# Analog_Switch_Arrays.net
KiCad netlist of a schematic drawn in Altium Designer
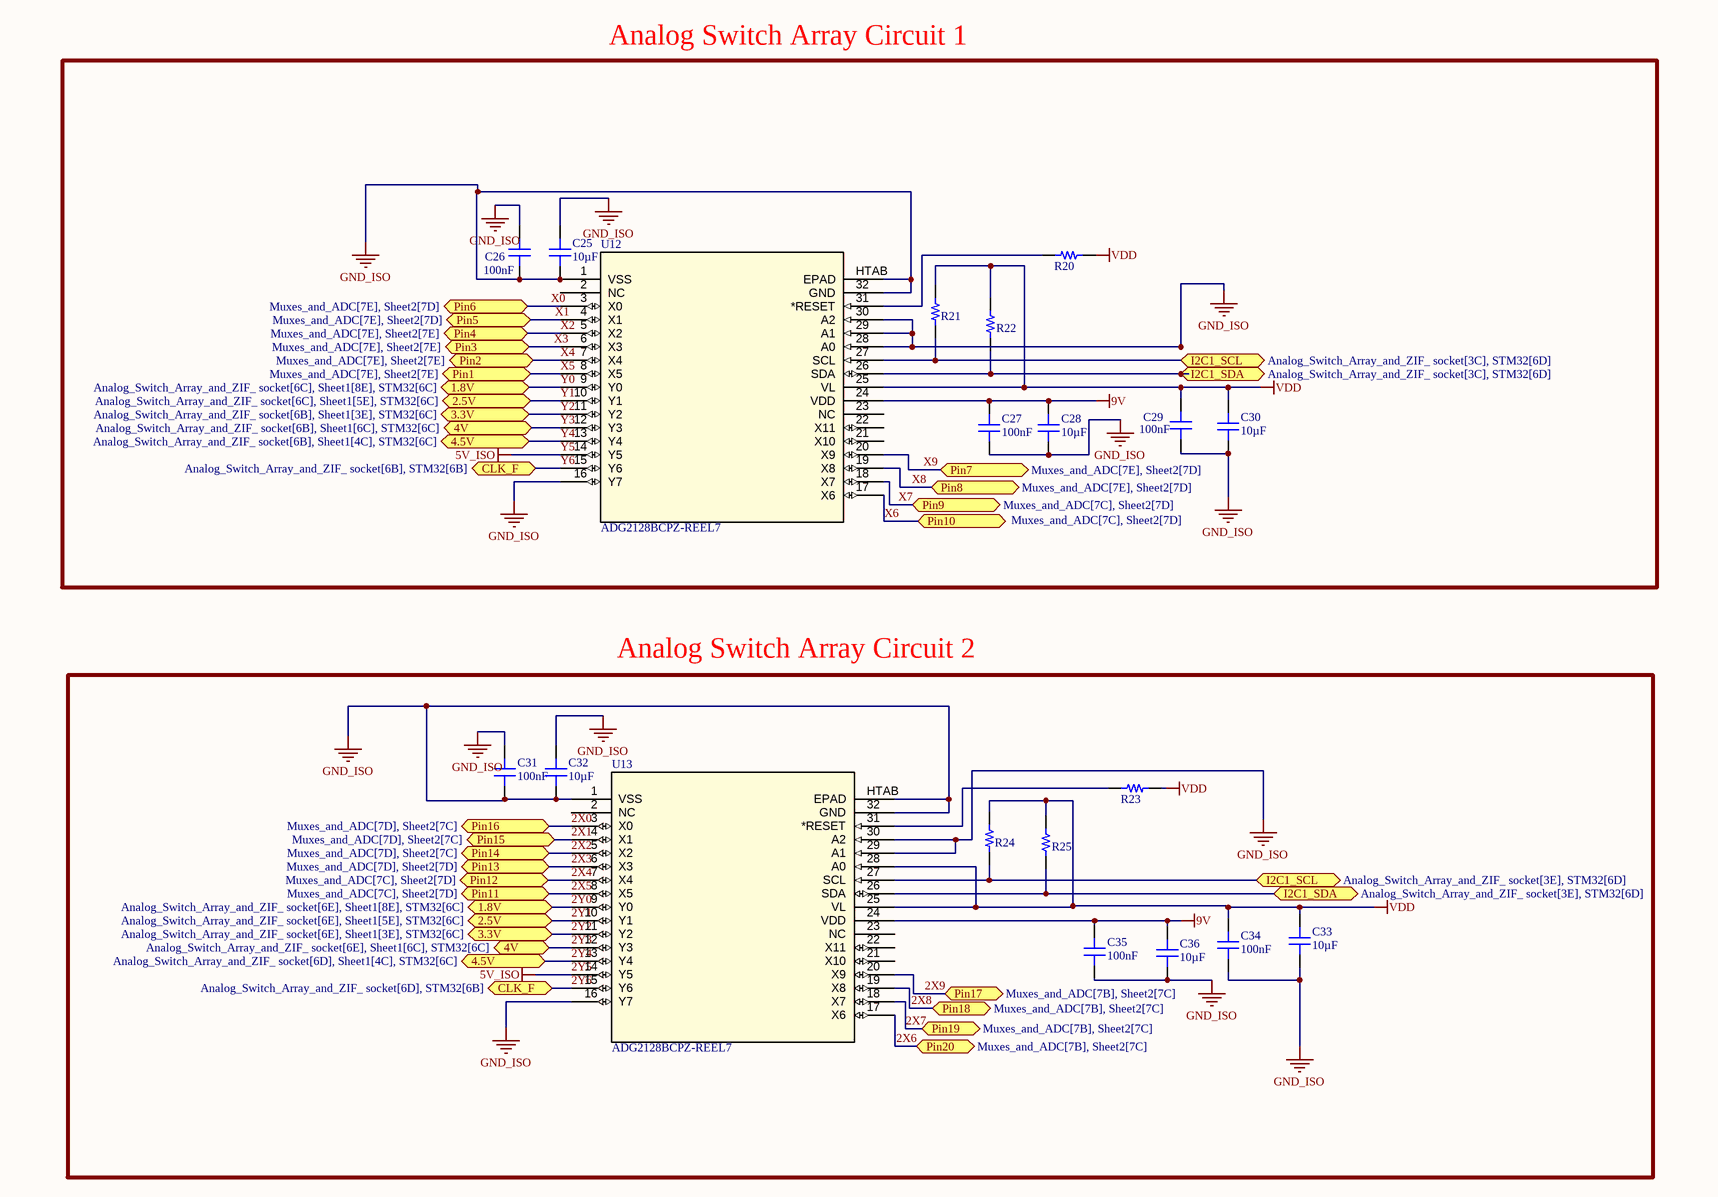
[diagram p0: Analog_Switch_Arrays.SchDoc]

(export (version "E")
  (design (tool "Eeschema 10.0.6"))
  (components
    (comp (ref "C25")
      (value "10µF")
      (footprint "MURATA CAP GCM31M 1206_3216")
      (description "CAP CER 10UF 35V X8M 1206")
      (fields (field (name "PART NUMBER") "GCM31CM8EG106KE08L"))
      (libsource (lib "University of Massachusetts Lowell") (part "CAPACITOR"))
    )
    (comp (ref "C26")
      (value "100nF")
      (footprint "CAP 1206_3216 - 0.8MM")
      (description "CAP CER 1206 0.1F 16V ULTRA STAB")
      (fields (field (name "PART NUMBER") "C1206X104G4HAC7800"))
      (libsource (lib "University of Massachusetts Lowell") (part "CAPACITOR"))
    )
    (comp (ref "C27")
      (value "100nF")
      (footprint "CAP 1206_3216 - 0.8MM")
      (description "CAP CER 1206 0.1F 16V ULTRA STAB")
      (fields (field (name "PART NUMBER") "C1206X104G4HAC7800"))
      (libsource (lib "University of Massachusetts Lowell") (part "CAPACITOR"))
    )
    (comp (ref "C28")
      (value "10µF")
      (footprint "MURATA CAP GCM31M 1206_3216")
      (description "CAP CER 10UF 35V X8M 1206")
      (fields (field (name "PART NUMBER") "GCM31CM8EG106KE08L"))
      (libsource (lib "University of Massachusetts Lowell") (part "CAPACITOR"))
    )
    (comp (ref "C29")
      (value "100nF")
      (footprint "CAP 1206_3216 - 0.8MM")
      (description "CAP CER 1206 0.1F 16V ULTRA STAB")
      (fields (field (name "PART NUMBER") "C1206X104G4HAC7800"))
      (libsource (lib "University of Massachusetts Lowell") (part "CAPACITOR"))
    )
    (comp (ref "C30")
      (value "10µF")
      (footprint "MURATA CAP GCM31M 1206_3216")
      (description "CAP CER 10UF 35V X8M 1206")
      (fields (field (name "PART NUMBER") "GCM31CM8EG106KE08L"))
      (libsource (lib "University of Massachusetts Lowell") (part "CAPACITOR"))
    )
    (comp (ref "C31")
      (value "100nF")
      (footprint "CAP 1206_3216 - 0.8MM")
      (description "CAP CER 1206 0.1F 16V ULTRA STAB")
      (fields (field (name "PART NUMBER") "C1206X104G4HAC7800"))
      (libsource (lib "University of Massachusetts Lowell") (part "CAPACITOR"))
    )
    (comp (ref "C32")
      (value "10µF")
      (footprint "MURATA CAP GCM31M 1206_3216")
      (description "CAP CER 10UF 35V X8M 1206")
      (fields (field (name "PART NUMBER") "GCM31CM8EG106KE08L"))
      (libsource (lib "University of Massachusetts Lowell") (part "CAPACITOR"))
    )
    (comp (ref "C33")
      (value "10µF")
      (footprint "MURATA CAP GCM31M 1206_3216")
      (description "CAP CER 10UF 35V X8M 1206")
      (fields (field (name "PART NUMBER") "GCM31CM8EG106KE08L"))
      (libsource (lib "University of Massachusetts Lowell") (part "CAPACITOR"))
    )
    (comp (ref "C34")
      (value "100nF")
      (footprint "CAP 1206_3216 - 0.8MM")
      (description "CAP CER 1206 0.1F 16V ULTRA STAB")
      (fields (field (name "PART NUMBER") "C1206X104G4HAC7800"))
      (libsource (lib "University of Massachusetts Lowell") (part "CAPACITOR"))
    )
    (comp (ref "C35")
      (value "100nF")
      (footprint "CAP 1206_3216 - 0.8MM")
      (description "CAP CER 1206 0.1F 16V ULTRA STAB")
      (fields (field (name "PART NUMBER") "C1206X104G4HAC7800"))
      (libsource (lib "University of Massachusetts Lowell") (part "CAPACITOR"))
    )
    (comp (ref "C36")
      (value "10µF")
      (footprint "MURATA CAP GCM31M 1206_3216")
      (description "CAP CER 10UF 35V X8M 1206")
      (fields (field (name "PART NUMBER") "GCM31CM8EG106KE08L"))
      (libsource (lib "University of Massachusetts Lowell") (part "CAPACITOR"))
    )
    (comp (ref "R20")
      (value "RP1206BRD0710KL")
      (footprint "YAGEO RES 1206_3216")
      (description "RES 10K OHM 0.1% 1/4W 1206")
      (libsource (lib "University of Massachusetts Lowell") (part "RESISTOR"))
    )
    (comp (ref "R21")
      (value "SG732ETTD222K")
      (footprint "RES 1210_3225")
      (description "RES 2.2K OHM 10% 1/2W 1210")
      (libsource (lib "University of Massachusetts Lowell") (part "RESISTOR"))
    )
    (comp (ref "R22")
      (value "SG732ETTD222K")
      (footprint "RES 1210_3225")
      (description "RES 2.2K OHM 10% 1/2W 1210")
      (libsource (lib "University of Massachusetts Lowell") (part "RESISTOR"))
    )
    (comp (ref "R23")
      (value "RP1206BRD0710KL")
      (footprint "YAGEO RES 1206_3216")
      (description "RES 10K OHM 0.1% 1/4W 1206")
      (libsource (lib "University of Massachusetts Lowell") (part "RESISTOR"))
    )
    (comp (ref "R24")
      (value "SG732ETTD222K")
      (footprint "RES 1210_3225")
      (description "RES 2.2K OHM 10% 1/2W 1210")
      (libsource (lib "University of Massachusetts Lowell") (part "RESISTOR"))
    )
    (comp (ref "R25")
      (value "SG732ETTD222K")
      (footprint "RES 1210_3225")
      (description "RES 2.2K OHM 10% 1/2W 1210")
      (libsource (lib "University of Massachusetts Lowell") (part "RESISTOR"))
    )
    (comp (ref "U12")
      (value "ADG2128BCPZ-REEL7")
      (footprint "CP_32_7_ADI")
      (description "I2C CMOS 8 X 12 Analog Switch Array with Dual/Single Supplies")
      (fields (field (name "COPYRIGHT") "Copyright (C) 2025 Ultra Librarian. All rights reserved."))
      (libsource (lib "University of Massachusetts Lowell") (part "ADG2128BCPZ-REEL7"))
    )
    (comp (ref "U13")
      (value "ADG2128BCPZ-REEL7")
      (footprint "CP_32_7_ADI")
      (description "I2C CMOS 8 X 12 Analog Switch Array with Dual/Single Supplies")
      (fields (field (name "COPYRIGHT") "Copyright (C) 2025 Ultra Librarian. All rights reserved."))
      (libsource (lib "University of Massachusetts Lowell") (part "ADG2128BCPZ-REEL7"))
    )
  )
  (nets
    (net (code "1") (name "/2X0") (class "Default")
      (node (ref "U13") (pin "3") (pinfunction "X0_3") (pintype "bidirectional"))
    )
    (net (code "2") (name "/2X1") (class "Default")
      (node (ref "U13") (pin "4") (pinfunction "X1_4") (pintype "bidirectional"))
    )
    (net (code "3") (name "/2X2") (class "Default")
      (node (ref "U13") (pin "5") (pinfunction "X2_5") (pintype "bidirectional"))
    )
    (net (code "4") (name "/2X3") (class "Default")
      (node (ref "U13") (pin "6") (pinfunction "X3_6") (pintype "bidirectional"))
    )
    (net (code "5") (name "/2X4") (class "Default")
      (node (ref "U13") (pin "7") (pinfunction "X4_7") (pintype "bidirectional"))
    )
    (net (code "6") (name "/2X5") (class "Default")
      (node (ref "U13") (pin "8") (pinfunction "X5_8") (pintype "bidirectional"))
    )
    (net (code "7") (name "/2X6") (class "Default")
      (node (ref "U13") (pin "17") (pinfunction "X6_17") (pintype "bidirectional"))
    )
    (net (code "8") (name "/2X7") (class "Default")
      (node (ref "U13") (pin "18") (pinfunction "X7_18") (pintype "bidirectional"))
    )
    (net (code "9") (name "/2X8") (class "Default")
      (node (ref "U13") (pin "19") (pinfunction "X8_19") (pintype "bidirectional"))
    )
    (net (code "10") (name "/2X9") (class "Default")
      (node (ref "U13") (pin "20") (pinfunction "X9_20") (pintype "bidirectional"))
    )
    (net (code "11") (name "/2Y0") (class "Default")
      (node (ref "U12") (pin "9") (pinfunction "Y0_9") (pintype "bidirectional"))
      (node (ref "U13") (pin "9") (pinfunction "Y0_9") (pintype "bidirectional"))
    )
    (net (code "12") (name "/2Y1") (class "Default")
      (node (ref "U12") (pin "10") (pinfunction "Y1_10") (pintype "bidirectional"))
      (node (ref "U13") (pin "10") (pinfunction "Y1_10") (pintype "bidirectional"))
    )
    (net (code "13") (name "/2Y2") (class "Default")
      (node (ref "U12") (pin "11") (pinfunction "Y2_11") (pintype "bidirectional"))
      (node (ref "U13") (pin "11") (pinfunction "Y2_11") (pintype "bidirectional"))
    )
    (net (code "14") (name "/2Y3") (class "Default")
      (node (ref "U12") (pin "12") (pinfunction "Y3_12") (pintype "bidirectional"))
      (node (ref "U13") (pin "12") (pinfunction "Y3_12") (pintype "bidirectional"))
    )
    (net (code "15") (name "/2Y4") (class "Default")
      (node (ref "U12") (pin "13") (pinfunction "Y4_13") (pintype "bidirectional"))
      (node (ref "U13") (pin "13") (pinfunction "Y4_13") (pintype "bidirectional"))
    )
    (net (code "16") (name "/2Y6") (class "Default")
      (node (ref "U12") (pin "15") (pinfunction "Y6_15") (pintype "bidirectional"))
      (node (ref "U13") (pin "15") (pinfunction "Y6_15") (pintype "bidirectional"))
    )
    (net (code "17") (name "/I2C1_SCL") (class "Default")
      (node (ref "R21") (pin "1") (pinfunction "1_1") (pintype "passive"))
      (node (ref "R24") (pin "1") (pinfunction "1_1") (pintype "passive"))
      (node (ref "U12") (pin "27") (pinfunction "SCL_27") (pintype "input"))
      (node (ref "U13") (pin "27") (pinfunction "SCL_27") (pintype "input"))
    )
    (net (code "18") (name "/I2C1_SDA") (class "Default")
      (node (ref "R22") (pin "1") (pinfunction "1_1") (pintype "passive"))
      (node (ref "R25") (pin "1") (pinfunction "1_1") (pintype "passive"))
      (node (ref "U12") (pin "26") (pinfunction "SDA_26") (pintype "bidirectional"))
      (node (ref "U13") (pin "26") (pinfunction "SDA_26") (pintype "bidirectional"))
    )
    (net (code "19") (name "/X0") (class "Default")
      (node (ref "U12") (pin "3") (pinfunction "X0_3") (pintype "bidirectional"))
    )
    (net (code "20") (name "/X1") (class "Default")
      (node (ref "U12") (pin "4") (pinfunction "X1_4") (pintype "bidirectional"))
    )
    (net (code "21") (name "/X2") (class "Default")
      (node (ref "U12") (pin "5") (pinfunction "X2_5") (pintype "bidirectional"))
    )
    (net (code "22") (name "/X3") (class "Default")
      (node (ref "U12") (pin "6") (pinfunction "X3_6") (pintype "bidirectional"))
    )
    (net (code "23") (name "/X4") (class "Default")
      (node (ref "U12") (pin "7") (pinfunction "X4_7") (pintype "bidirectional"))
    )
    (net (code "24") (name "/X5") (class "Default")
      (node (ref "U12") (pin "8") (pinfunction "X5_8") (pintype "bidirectional"))
    )
    (net (code "25") (name "/X6") (class "Default")
      (node (ref "U12") (pin "17") (pinfunction "X6_17") (pintype "bidirectional"))
    )
    (net (code "26") (name "/X7") (class "Default")
      (node (ref "U12") (pin "18") (pinfunction "X7_18") (pintype "bidirectional"))
    )
    (net (code "27") (name "/X8") (class "Default")
      (node (ref "U12") (pin "19") (pinfunction "X8_19") (pintype "bidirectional"))
    )
    (net (code "28") (name "/X9") (class "Default")
      (node (ref "U12") (pin "20") (pinfunction "X9_20") (pintype "bidirectional"))
    )
    (net (code "29") (name "5V_ISO") (class "Default")
      (node (ref "U12") (pin "14") (pinfunction "Y5_14") (pintype "bidirectional"))
      (node (ref "U13") (pin "14") (pinfunction "Y5_14") (pintype "bidirectional"))
    )
    (net (code "30") (name "9V") (class "Default")
      (node (ref "C27") (pin "2") (pinfunction "2_2") (pintype "passive"))
      (node (ref "C28") (pin "2") (pinfunction "2_2") (pintype "passive"))
      (node (ref "C35") (pin "2") (pinfunction "2_2") (pintype "passive"))
      (node (ref "C36") (pin "2") (pinfunction "2_2") (pintype "passive"))
      (node (ref "U12") (pin "24") (pinfunction "VDD_24") (pintype "power_in"))
      (node (ref "U13") (pin "24") (pinfunction "VDD_24") (pintype "power_in"))
    )
    (net (code "31") (name "GND_ISO") (class "Default")
      (node (ref "C25") (pin "1") (pinfunction "1_1") (pintype "passive"))
      (node (ref "C25") (pin "2") (pinfunction "2_2") (pintype "passive"))
      (node (ref "C26") (pin "1") (pinfunction "1_1") (pintype "passive"))
      (node (ref "C26") (pin "2") (pinfunction "2_2") (pintype "passive"))
      (node (ref "C27") (pin "1") (pinfunction "1_1") (pintype "passive"))
      (node (ref "C28") (pin "1") (pinfunction "1_1") (pintype "passive"))
      (node (ref "C29") (pin "1") (pinfunction "1_1") (pintype "passive"))
      (node (ref "C30") (pin "1") (pinfunction "1_1") (pintype "passive"))
      (node (ref "C31") (pin "1") (pinfunction "1_1") (pintype "passive"))
      (node (ref "C31") (pin "2") (pinfunction "2_2") (pintype "passive"))
      (node (ref "C32") (pin "1") (pinfunction "1_1") (pintype "passive"))
      (node (ref "C32") (pin "2") (pinfunction "2_2") (pintype "passive"))
      (node (ref "C33") (pin "1") (pinfunction "1_1") (pintype "passive"))
      (node (ref "C34") (pin "1") (pinfunction "1_1") (pintype "passive"))
      (node (ref "C35") (pin "1") (pinfunction "1_1") (pintype "passive"))
      (node (ref "C36") (pin "1") (pinfunction "1_1") (pintype "passive"))
      (node (ref "U12") (pin "1") (pinfunction "VSS_1") (pintype "power_in"))
      (node (ref "U12") (pin "16") (pinfunction "Y7_16") (pintype "bidirectional"))
      (node (ref "U12") (pin "28") (pinfunction "A0_28") (pintype "input"))
      (node (ref "U12") (pin "29") (pinfunction "A1_29") (pintype "input"))
      (node (ref "U12") (pin "30") (pinfunction "A2_30") (pintype "input"))
      (node (ref "U12") (pin "32") (pinfunction "GND_32") (pintype "power_in"))
      (node (ref "U12") (pin "HTAB") (pinfunction "EPAD_HTAB") (pintype "passive"))
      (node (ref "U13") (pin "1") (pinfunction "VSS_1") (pintype "power_in"))
      (node (ref "U13") (pin "16") (pinfunction "Y7_16") (pintype "bidirectional"))
      (node (ref "U13") (pin "29") (pinfunction "A1_29") (pintype "input"))
      (node (ref "U13") (pin "30") (pinfunction "A2_30") (pintype "input"))
      (node (ref "U13") (pin "32") (pinfunction "GND_32") (pintype "power_in"))
      (node (ref "U13") (pin "HTAB") (pinfunction "EPAD_HTAB") (pintype "passive"))
    )
    (net (code "32") (name "Net-(U12-*RESET)") (class "Default")
      (node (ref "R20") (pin "1") (pinfunction "1_1") (pintype "passive"))
      (node (ref "U12") (pin "31") (pinfunction "*RESET_31") (pintype "input"))
    )
    (net (code "33") (name "Net-(U13-*RESET)") (class "Default")
      (node (ref "R23") (pin "1") (pinfunction "1_1") (pintype "passive"))
      (node (ref "U13") (pin "31") (pinfunction "*RESET_31") (pintype "input"))
    )
    (net (code "34") (name "VDD") (class "Default")
      (node (ref "C29") (pin "2") (pinfunction "2_2") (pintype "passive"))
      (node (ref "C30") (pin "2") (pinfunction "2_2") (pintype "passive"))
      (node (ref "C33") (pin "2") (pinfunction "2_2") (pintype "passive"))
      (node (ref "C34") (pin "2") (pinfunction "2_2") (pintype "passive"))
      (node (ref "R20") (pin "2") (pinfunction "2_2") (pintype "passive"))
      (node (ref "R21") (pin "2") (pinfunction "2_2") (pintype "passive"))
      (node (ref "R22") (pin "2") (pinfunction "2_2") (pintype "passive"))
      (node (ref "R23") (pin "2") (pinfunction "2_2") (pintype "passive"))
      (node (ref "R24") (pin "2") (pinfunction "2_2") (pintype "passive"))
      (node (ref "R25") (pin "2") (pinfunction "2_2") (pintype "passive"))
      (node (ref "U12") (pin "25") (pinfunction "VL_25") (pintype "power_in"))
      (node (ref "U13") (pin "25") (pinfunction "VL_25") (pintype "power_in"))
      (node (ref "U13") (pin "28") (pinfunction "A0_28") (pintype "input"))
    )
    (net (code "35") (name "unconnected-(U12-NC-Pad2)") (class "Default")
      (node (ref "U12") (pin "2") (pinfunction "NC_2") (pintype "passive"))
    )
    (net (code "36") (name "unconnected-(U12-NC-Pad23)") (class "Default")
      (node (ref "U12") (pin "23") (pinfunction "NC_23") (pintype "passive"))
    )
    (net (code "37") (name "unconnected-(U12-X10-Pad21)") (class "Default")
      (node (ref "U12") (pin "21") (pinfunction "X10_21") (pintype "bidirectional"))
    )
    (net (code "38") (name "unconnected-(U12-X11-Pad22)") (class "Default")
      (node (ref "U12") (pin "22") (pinfunction "X11_22") (pintype "bidirectional"))
    )
    (net (code "39") (name "unconnected-(U13-NC-Pad2)") (class "Default")
      (node (ref "U13") (pin "2") (pinfunction "NC_2") (pintype "passive"))
    )
    (net (code "40") (name "unconnected-(U13-NC-Pad23)") (class "Default")
      (node (ref "U13") (pin "23") (pinfunction "NC_23") (pintype "passive"))
    )
    (net (code "41") (name "unconnected-(U13-X10-Pad21)") (class "Default")
      (node (ref "U13") (pin "21") (pinfunction "X10_21") (pintype "bidirectional"))
    )
    (net (code "42") (name "unconnected-(U13-X11-Pad22)") (class "Default")
      (node (ref "U13") (pin "22") (pinfunction "X11_22") (pintype "bidirectional"))
    )
  )
)
